# fonte.net
KiCad netlist of a schematic drawn in EAGLE
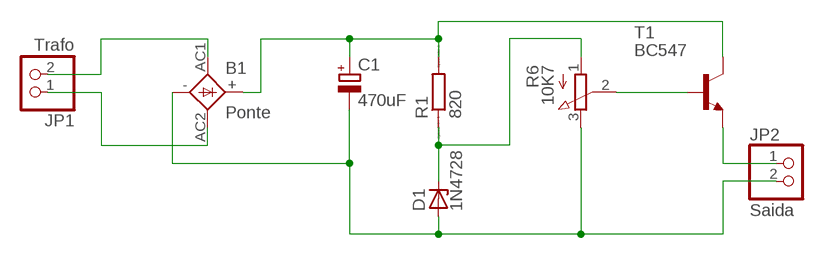
[diagram p0: schematic, sheet 1]

(export (version "E")
  (design (tool "Eeschema 10.0.6"))
  (components
    (comp (ref "B1")
      (value "Ponte")
      (footprint "eagle-import:1KAB")
      (libsource (lib "eagle-import") (part "1KAB"))
    )
    (comp (ref "C1")
      (value "470uF")
      (footprint "eagle-import:E5-10,5")
      (libsource (lib "eagle-import") (part "CPOL-EUE5-10.5"))
    )
    (comp (ref "D1")
      (value "1N4728")
      (footprint "eagle-import:DO41Z10")
      (libsource (lib "eagle-import") (part "1N4728"))
    )
    (comp (ref "JP1")
      (value "Trafo")
      (footprint "eagle-import:1X02")
      (libsource (lib "eagle-import") (part "PINHD-1X2"))
    )
    (comp (ref "JP2")
      (value "Saida")
      (footprint "eagle-import:1X02")
      (libsource (lib "eagle-import") (part "PINHD-1X2"))
    )
    (comp (ref "R1")
      (value "820")
      (footprint "eagle-import:0207_10")
      (libsource (lib "eagle-import") (part "R0207/10"))
    )
    (comp (ref "R6")
      (value "10K7")
      (footprint "eagle-import:3RP_1610N")
      (libsource (lib "eagle-import") (part "3RP/1610N"))
    )
    (comp (ref "T1")
      (value "BC547")
      (footprint "eagle-import:TO92")
      (libsource (lib "eagle-import") (part "BC547"))
    )
  )
  (nets
    (net (code "1") (name "Net-(B1-PadAC1)") (class "Default")
      (node (ref "B1") (pin "AC1") (pinfunction "AC1_AC1") (pintype "passive"))
      (node (ref "JP1") (pin "2") (pinfunction "2_2") (pintype "passive"))
    )
    (net (code "2") (name "Net-(B1-PadAC2)") (class "Default")
      (node (ref "B1") (pin "AC2") (pinfunction "AC2_AC2") (pintype "passive"))
      (node (ref "JP1") (pin "1") (pinfunction "1_1") (pintype "passive"))
    )
    (net (code "3") (name "Net-(R6-A)") (class "Default")
      (node (ref "D1") (pin "C") (pinfunction "C_C") (pintype "passive"))
      (node (ref "R1") (pin "1") (pinfunction "1_1") (pintype "passive"))
      (node (ref "R6") (pin "1") (pinfunction "A_1") (pintype "passive"))
    )
    (net (code "4") (name "Net-(R6-E)") (class "Default")
      (node (ref "B1") (pin "-") (pinfunction "-_-") (pintype "passive"))
      (node (ref "C1") (pin "-") (pinfunction "-_-") (pintype "passive"))
      (node (ref "D1") (pin "A") (pinfunction "A_A") (pintype "passive"))
      (node (ref "JP2") (pin "2") (pinfunction "2_2") (pintype "passive"))
      (node (ref "R6") (pin "3") (pinfunction "E_3") (pintype "passive"))
    )
    (net (code "5") (name "Net-(R6-S)") (class "Default")
      (node (ref "R6") (pin "2") (pinfunction "S_2") (pintype "passive"))
      (node (ref "T1") (pin "2") (pinfunction "B_2") (pintype "passive"))
    )
    (net (code "6") (name "Net-(T1-C)") (class "Default")
      (node (ref "B1") (pin "+") (pinfunction "+_+") (pintype "passive"))
      (node (ref "C1") (pin "+") (pinfunction "+_+") (pintype "passive"))
      (node (ref "R1") (pin "2") (pinfunction "2_2") (pintype "passive"))
      (node (ref "T1") (pin "3") (pinfunction "C_3") (pintype "passive"))
    )
    (net (code "7") (name "Net-(T1-E)") (class "Default")
      (node (ref "JP2") (pin "1") (pinfunction "1_1") (pintype "passive"))
      (node (ref "T1") (pin "1") (pinfunction "E_1") (pintype "passive"))
    )
  )
)
